# control.net
KiCad netlist of a schematic drawn in EAGLE
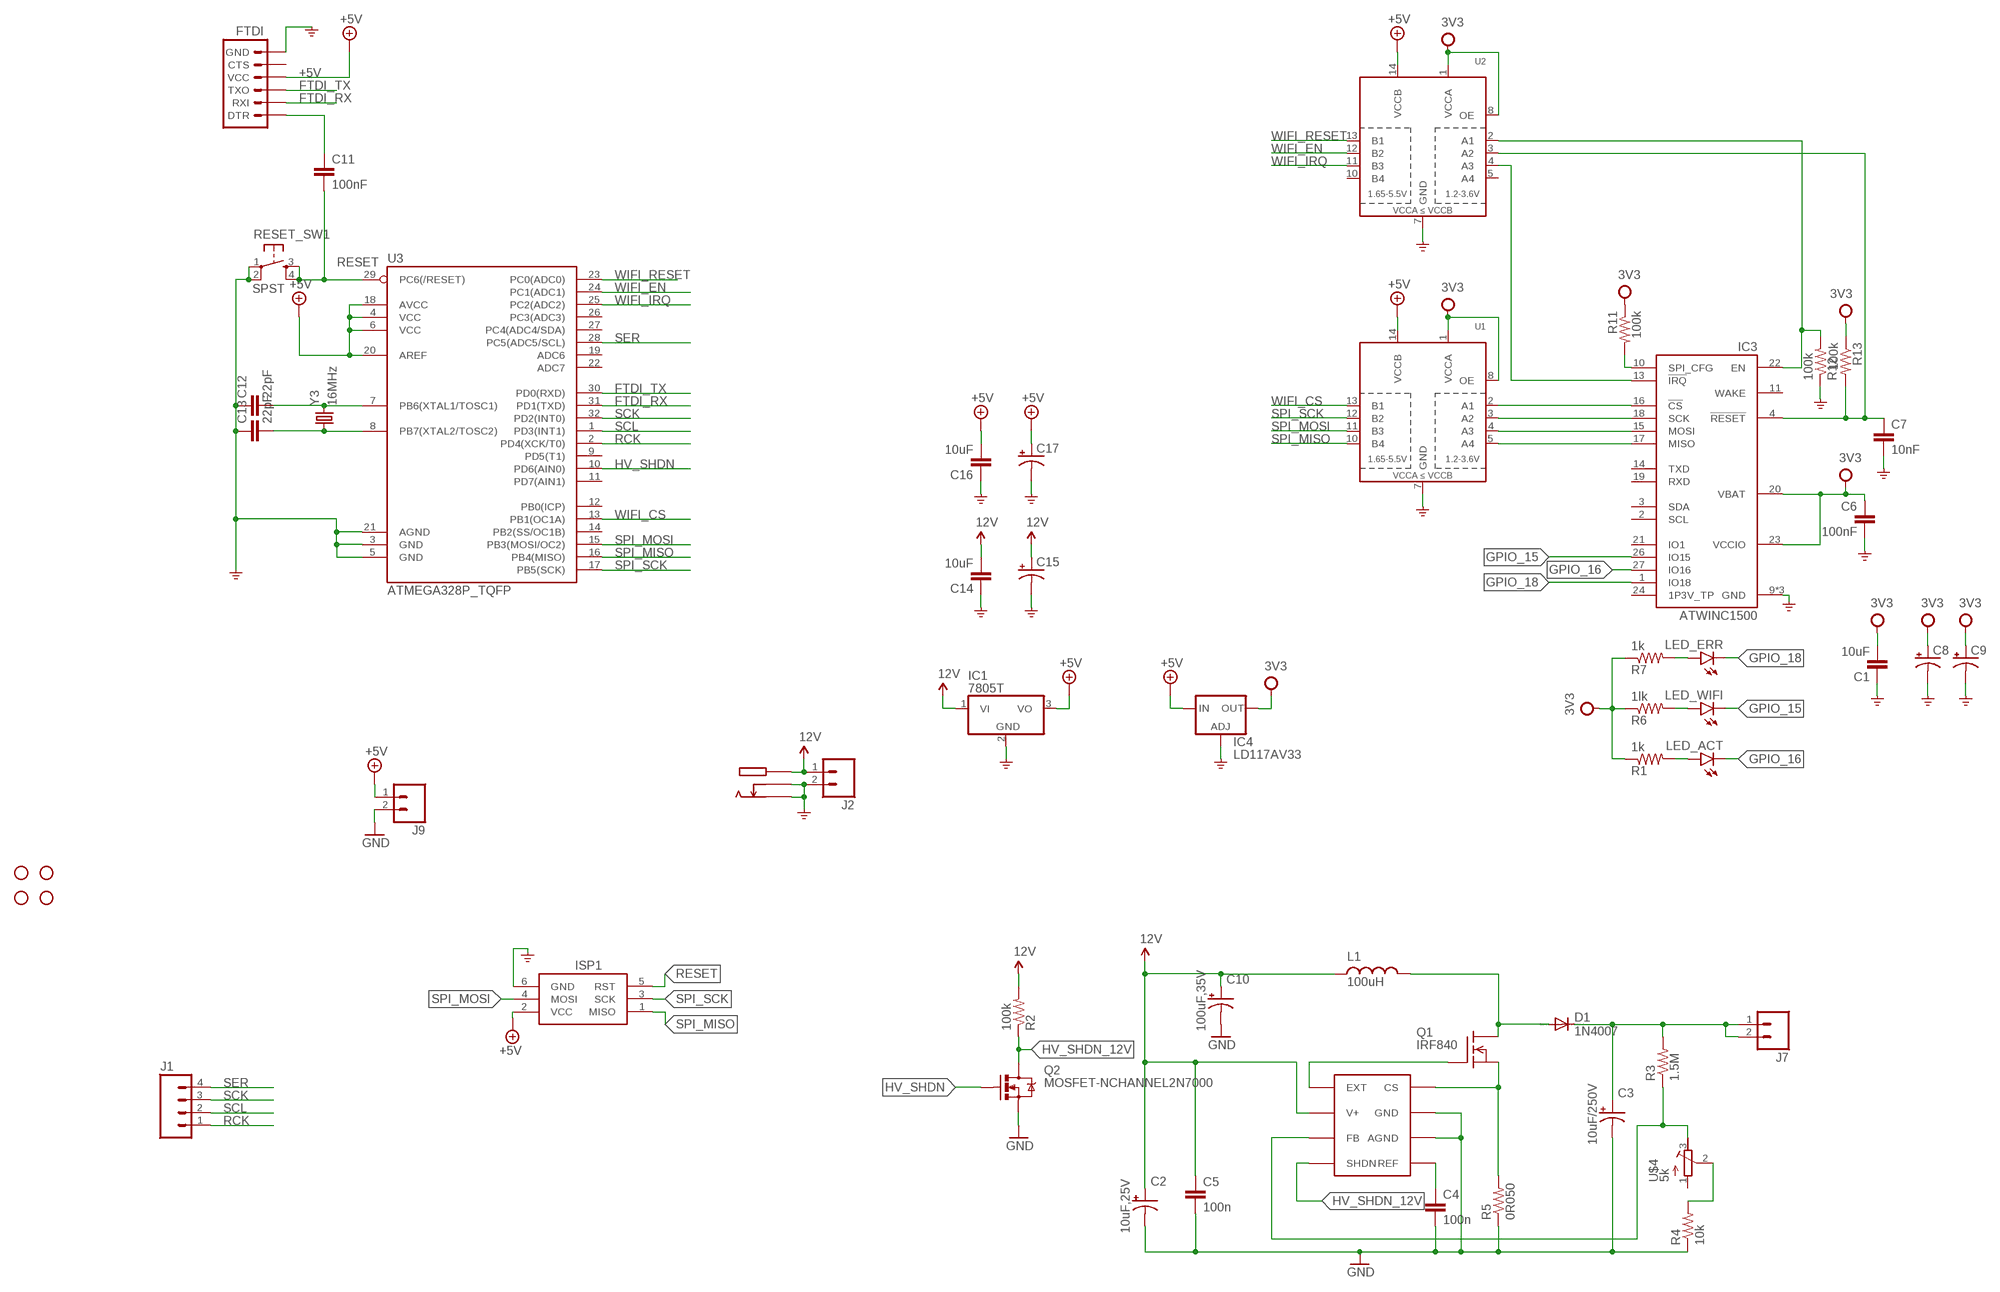
[diagram p0: schematic, sheet 1]

(export (version "E")
  (design (tool "Eeschema 10.0.6"))
  (components
    (comp (ref "C1")
      (value "10uF")
      (footprint "eagle-import:0805")
      (libsource (lib "eagle-import") (part "CAP0805"))
    )
    (comp (ref "C2")
      (value "10uF,25V")
      (footprint "eagle-import:CPOL-RADIAL-10UF-25V")
      (libsource (lib "eagle-import") (part "CAP_POLPTH2"))
    )
    (comp (ref "C3")
      (value "10uF/250V")
      (footprint "eagle-import:CPOL-RADIAL-10UF-25V")
      (libsource (lib "eagle-import") (part "CAP_POLPTH2"))
    )
    (comp (ref "C4")
      (value "100n")
      (footprint "eagle-import:CAP-PTH-SMALL")
      (libsource (lib "eagle-import") (part "SparkFun-Passives_CAPPTH"))
    )
    (comp (ref "C5")
      (value "100n")
      (footprint "eagle-import:CAP-PTH-SMALL")
      (libsource (lib "eagle-import") (part "SparkFun-Passives_CAPPTH"))
    )
    (comp (ref "C6")
      (value "100nF")
      (footprint "eagle-import:0805")
      (libsource (lib "eagle-import") (part "CAP0805"))
    )
    (comp (ref "C7")
      (value "10nF")
      (footprint "eagle-import:0805")
      (libsource (lib "eagle-import") (part "CAP0805"))
    )
    (comp (ref "C8")
      (value "CPOL-USE2,5-6E")
      (footprint "eagle-import:E2,5-6E")
      (libsource (lib "eagle-import") (part "CPOL-USE2,5-6E"))
    )
    (comp (ref "C9")
      (value "CPOL-USE2,5-6E")
      (footprint "eagle-import:E2,5-6E")
      (libsource (lib "eagle-import") (part "CPOL-USE2,5-6E"))
    )
    (comp (ref "C10")
      (value "100uF,35V")
      (footprint "eagle-import:CPOL-RADIAL-10UF-25V")
      (libsource (lib "eagle-import") (part "CAP_POLPTH2"))
    )
    (comp (ref "C11")
      (value "100nF")
      (footprint "eagle-import:0805")
      (libsource (lib "eagle-import") (part "CAP0805"))
    )
    (comp (ref "C12")
      (value "22pF")
      (footprint "eagle-import:0805")
      (libsource (lib "eagle-import") (part "CAP0805"))
    )
    (comp (ref "C13")
      (value "22pF")
      (footprint "eagle-import:0805")
      (libsource (lib "eagle-import") (part "CAP0805"))
    )
    (comp (ref "C14")
      (value "10uF")
      (footprint "eagle-import:0805")
      (libsource (lib "eagle-import") (part "CAP0805"))
    )
    (comp (ref "C15")
      (value "CPOL-USE2,5-6E")
      (footprint "eagle-import:E2,5-6E")
      (libsource (lib "eagle-import") (part "CPOL-USE2,5-6E"))
    )
    (comp (ref "C16")
      (value "10uF")
      (footprint "eagle-import:0805")
      (libsource (lib "eagle-import") (part "CAP0805"))
    )
    (comp (ref "C17")
      (value "CPOL-USE2,5-6E")
      (footprint "eagle-import:E2,5-6E")
      (libsource (lib "eagle-import") (part "CPOL-USE2,5-6E"))
    )
    (comp (ref "D1")
      (value "1N4007")
      (footprint "eagle-import:DO41-10")
      (libsource (lib "eagle-import") (part "1N4004"))
    )
    (comp (ref "FTDI")
      (value "ARDUINO_SERIAL_PROGRAMPTH")
      (footprint "eagle-import:1X06")
      (libsource (lib "eagle-import") (part "ARDUINO_SERIAL_PROGRAMPTH"))
    )
    (comp (ref "H1")
      (value "STAND-OFF")
      (footprint "eagle-import:STAND-OFF")
      (libsource (lib "eagle-import") (part "STAND-OFF"))
    )
    (comp (ref "H2")
      (value "STAND-OFF")
      (footprint "eagle-import:STAND-OFF")
      (libsource (lib "eagle-import") (part "STAND-OFF"))
    )
    (comp (ref "H3")
      (value "STAND-OFF")
      (footprint "eagle-import:STAND-OFF")
      (libsource (lib "eagle-import") (part "STAND-OFF"))
    )
    (comp (ref "H4")
      (value "STAND-OFF")
      (footprint "eagle-import:STAND-OFF")
      (libsource (lib "eagle-import") (part "STAND-OFF"))
    )
    (comp (ref "IC1")
      (value "7805T")
      (footprint "eagle-import:TO220H")
      (libsource (lib "eagle-import") (part "78T05"))
    )
    (comp (ref "IC3")
      (value "ATWINC1500")
      (footprint "eagle-import:ATWINC1500-MR210")
      (libsource (lib "eagle-import") (part "ATWINC1500"))
    )
    (comp (ref "IC4")
      (value "LD117AV33")
      (footprint "eagle-import:TO220L1")
      (libsource (lib "eagle-import") (part "LD117A?V33"))
    )
    (comp (ref "ISP1")
      (value "AVRISP-6")
      (footprint "eagle-import:AVRISP")
      (libsource (lib "eagle-import") (part "AVRISP-6"))
    )
    (comp (ref "J1")
      (value "M04PTH")
      (footprint "eagle-import:1X04")
      (libsource (lib "eagle-import") (part "M04PTH"))
    )
    (comp (ref "J2")
      (value "M02PTH")
      (footprint "eagle-import:1X02")
      (libsource (lib "eagle-import") (part "M02PTH"))
    )
    (comp (ref "J7")
      (value "M02PTH")
      (footprint "eagle-import:1X02")
      (libsource (lib "eagle-import") (part "M02PTH"))
    )
    (comp (ref "J9")
      (value "M02PTH")
      (footprint "eagle-import:1X02")
      (libsource (lib "eagle-import") (part "M02PTH"))
    )
    (comp (ref "L1")
      (value "100uH")
      (footprint "eagle-import:L-B82479")
      (libsource (lib "eagle-import") (part "L-SMT-POWER-B82479"))
    )
    (comp (ref "LED_ACT")
      (value "LED0603")
      (footprint "eagle-import:LED-0603")
      (libsource (lib "eagle-import") (part "LED0603"))
    )
    (comp (ref "LED_ERR")
      (value "LED0603")
      (footprint "eagle-import:LED-0603")
      (libsource (lib "eagle-import") (part "LED0603"))
    )
    (comp (ref "LED_WIFI")
      (value "LED0603")
      (footprint "eagle-import:LED-0603")
      (libsource (lib "eagle-import") (part "LED0603"))
    )
    (comp (ref "Q1")
      (value "IRF840")
      (footprint "eagle-import:TO220")
      (libsource (lib "eagle-import") (part "IRF840"))
    )
    (comp (ref "Q2")
      (value "MOSFET-NCHANNEL2N7000")
      (footprint "eagle-import:TO-92")
      (libsource (lib "eagle-import") (part "MOSFET-NCHANNEL2N7000"))
    )
    (comp (ref "R1")
      (value "1k")
      (footprint "eagle-import:0805")
      (libsource (lib "eagle-import") (part "RESISTOR0805-RES"))
    )
    (comp (ref "R2")
      (value "100k")
      (footprint "eagle-import:0805")
      (libsource (lib "eagle-import") (part "RESISTOR0805-RES"))
    )
    (comp (ref "R3")
      (value "1.5M")
      (footprint "eagle-import:AXIAL-0.4")
      (libsource (lib "eagle-import") (part "RESISTORPTH-1/4W"))
    )
    (comp (ref "R4")
      (value "10k")
      (footprint "eagle-import:AXIAL-0.4")
      (libsource (lib "eagle-import") (part "RESISTORPTH-1/4W"))
    )
    (comp (ref "R5")
      (value "0R050")
      (footprint "eagle-import:AXIAL-0.4")
      (libsource (lib "eagle-import") (part "RESISTORPTH-1/4W"))
    )
    (comp (ref "R6")
      (value "1lk")
      (footprint "eagle-import:0805")
      (libsource (lib "eagle-import") (part "RESISTOR0805-RES"))
    )
    (comp (ref "R7")
      (value "1k")
      (footprint "eagle-import:0805")
      (libsource (lib "eagle-import") (part "RESISTOR0805-RES"))
    )
    (comp (ref "R11")
      (value "100k")
      (footprint "eagle-import:0805")
      (libsource (lib "eagle-import") (part "RESISTOR0805-RES"))
    )
    (comp (ref "R12")
      (value "100k")
      (footprint "eagle-import:0805")
      (libsource (lib "eagle-import") (part "RESISTOR0805-RES"))
    )
    (comp (ref "R13")
      (value "100k")
      (footprint "eagle-import:0805")
      (libsource (lib "eagle-import") (part "RESISTOR0805-RES"))
    )
    (comp (ref "RESET_SW1")
      (value "SPST")
      (footprint "eagle-import:TAC-SWITCH-PTH")
      (libsource (lib "eagle-import") (part "TACTILE-SWITCH-PTH"))
    )
    (comp (ref "U$3")
      (value "MAX1771")
      (footprint "eagle-import:8-DIP")
      (libsource (lib "eagle-import") (part "MAX1771"))
    )
    (comp (ref "U$4")
      (value "5k")
      (footprint "eagle-import:RTRIM3362P")
      (libsource (lib "eagle-import") (part "RTRIM-3362P"))
    )
    (comp (ref "U$19")
      (value "PJ-044A")
      (footprint "eagle-import:PJ-044A")
      (libsource (lib "eagle-import") (part "PJ-044A"))
    )
    (comp (ref "U1")
      (value "TXB0104PWRSOIC14")
      (footprint "eagle-import:SO14")
      (libsource (lib "eagle-import") (part "TXB0104PWRSOIC14"))
    )
    (comp (ref "U2")
      (value "TXB0104PWRSOIC14")
      (footprint "eagle-import:SO14")
      (libsource (lib "eagle-import") (part "TXB0104PWRSOIC14"))
    )
    (comp (ref "U3")
      (value "ATMEGA328P_TQFP")
      (footprint "eagle-import:TQFP32-08")
      (libsource (lib "eagle-import") (part "ATMEGA328P_TQFP"))
    )
    (comp (ref "Y3")
      (value "16MHz")
      (footprint "eagle-import:HC49US")
      (libsource (lib "eagle-import") (part "CRYSTALHC49US"))
    )
  )
  (nets
    (net (code "1") (name "+5V") (class "Default")
      (node (ref "C16") (pin "2") (pinfunction "2_2") (pintype "passive"))
      (node (ref "C17") (pin "+") (pinfunction "+_+") (pintype "passive"))
      (node (ref "FTDI") (pin "4") (pinfunction "VCC_4") (pintype "passive"))
      (node (ref "IC1") (pin "3") (pinfunction "VO_3") (pintype "passive"))
      (node (ref "IC4") (pin "3") (pinfunction "IN_3") (pintype "input"))
      (node (ref "ISP1") (pin "2") (pinfunction "VCC_2") (pintype "power_in"))
      (node (ref "J9") (pin "1") (pinfunction "1_1") (pintype "passive"))
      (node (ref "U1") (pin "14") (pinfunction "VCCB_14") (pintype "bidirectional"))
      (node (ref "U2") (pin "14") (pinfunction "VCCB_14") (pintype "bidirectional"))
      (node (ref "U3") (pin "18") (pinfunction "AVCC_18") (pintype "bidirectional"))
      (node (ref "U3") (pin "20") (pinfunction "AREF_20") (pintype "bidirectional"))
      (node (ref "U3") (pin "4") (pinfunction "VCC_4") (pintype "bidirectional"))
      (node (ref "U3") (pin "6") (pinfunction "VCC_6") (pintype "bidirectional"))
    )
    (net (code "2") (name "/FTDI_RX") (class "Default")
      (node (ref "FTDI") (pin "2") (pinfunction "RXI_2") (pintype "passive"))
      (node (ref "U3") (pin "31") (pinfunction "PD1(TXD)_31") (pintype "bidirectional"))
    )
    (net (code "3") (name "/FTDI_TX") (class "Default")
      (node (ref "FTDI") (pin "3") (pinfunction "TXO_3") (pintype "passive"))
      (node (ref "U3") (pin "30") (pinfunction "PD0(RXD)_30") (pintype "bidirectional"))
    )
    (net (code "4") (name "/RCK") (class "Default")
      (node (ref "J1") (pin "1") (pinfunction "1_1") (pintype "passive"))
      (node (ref "U3") (pin "2") (pinfunction "PD4(XCK/T0)_2") (pintype "bidirectional"))
    )
    (net (code "5") (name "/SCK") (class "Default")
      (node (ref "J1") (pin "3") (pinfunction "3_3") (pintype "passive"))
      (node (ref "U3") (pin "32") (pinfunction "PD2(INT0)_32") (pintype "bidirectional"))
    )
    (net (code "6") (name "/SCL") (class "Default")
      (node (ref "J1") (pin "2") (pinfunction "2_2") (pintype "passive"))
      (node (ref "U3") (pin "1") (pinfunction "PD3(INT1)_1") (pintype "bidirectional"))
    )
    (net (code "7") (name "/SER") (class "Default")
      (node (ref "J1") (pin "4") (pinfunction "4_4") (pintype "passive"))
      (node (ref "U3") (pin "28") (pinfunction "PC5(ADC5/SCL)_28") (pintype "bidirectional"))
    )
    (net (code "8") (name "/WIFI_CS") (class "Default")
      (node (ref "U1") (pin "13") (pinfunction "B1_13") (pintype "bidirectional"))
      (node (ref "U3") (pin "13") (pinfunction "PB1(OC1A)_13") (pintype "bidirectional"))
    )
    (net (code "9") (name "/WIFI_EN") (class "Default")
      (node (ref "U2") (pin "12") (pinfunction "B2_12") (pintype "bidirectional"))
      (node (ref "U3") (pin "24") (pinfunction "PC1(ADC1)_24") (pintype "bidirectional"))
    )
    (net (code "10") (name "/WIFI_IRQ") (class "Default")
      (node (ref "U2") (pin "11") (pinfunction "B3_11") (pintype "bidirectional"))
      (node (ref "U3") (pin "25") (pinfunction "PC2(ADC2)_25") (pintype "bidirectional"))
    )
    (net (code "11") (name "/WIFI_RESET") (class "Default")
      (node (ref "U2") (pin "13") (pinfunction "B1_13") (pintype "bidirectional"))
      (node (ref "U3") (pin "23") (pinfunction "PC0(ADC0)_23") (pintype "bidirectional"))
    )
    (net (code "12") (name "3V3") (class "Default")
      (node (ref "C1") (pin "2") (pinfunction "2_2") (pintype "passive"))
      (node (ref "C6") (pin "1") (pinfunction "1_1") (pintype "passive"))
      (node (ref "C8") (pin "+") (pinfunction "+_+") (pintype "passive"))
      (node (ref "C9") (pin "+") (pinfunction "+_+") (pintype "passive"))
      (node (ref "IC3") (pin "20") (pinfunction "VBAT_20") (pintype "power_in"))
      (node (ref "IC3") (pin "23") (pinfunction "VCCIO_23") (pintype "power_in"))
      (node (ref "IC4") (pin "2") (pinfunction "OUT_2") (pintype "passive"))
      (node (ref "R1") (pin "1") (pinfunction "1_1") (pintype "passive"))
      (node (ref "R11") (pin "1") (pinfunction "1_1") (pintype "passive"))
      (node (ref "R13") (pin "1") (pinfunction "1_1") (pintype "passive"))
      (node (ref "R6") (pin "1") (pinfunction "1_1") (pintype "passive"))
      (node (ref "R7") (pin "1") (pinfunction "1_1") (pintype "passive"))
      (node (ref "U1") (pin "1") (pinfunction "VCCA_1") (pintype "bidirectional"))
      (node (ref "U1") (pin "8") (pinfunction "OE_8") (pintype "bidirectional"))
      (node (ref "U2") (pin "1") (pinfunction "VCCA_1") (pintype "bidirectional"))
      (node (ref "U2") (pin "8") (pinfunction "OE_8") (pintype "bidirectional"))
    )
    (net (code "13") (name "12V") (class "Default")
      (node (ref "C10") (pin "1") (pinfunction "+_1") (pintype "passive"))
      (node (ref "C14") (pin "2") (pinfunction "2_2") (pintype "passive"))
      (node (ref "C15") (pin "+") (pinfunction "+_+") (pintype "passive"))
      (node (ref "C2") (pin "1") (pinfunction "+_1") (pintype "passive"))
      (node (ref "C5") (pin "1") (pinfunction "1_1") (pintype "passive"))
      (node (ref "IC1") (pin "1") (pinfunction "VI_1") (pintype "input"))
      (node (ref "J2") (pin "1") (pinfunction "1_1") (pintype "passive"))
      (node (ref "L1") (pin "P$1") (pinfunction "1_P$1") (pintype "passive"))
      (node (ref "R2") (pin "2") (pinfunction "2_2") (pintype "passive"))
      (node (ref "U$19") (pin "1") (pinfunction "1_1") (pintype "bidirectional"))
      (node (ref "U$19") (pin "P1") (pinfunction "1_P1") (pintype "bidirectional"))
      (node (ref "U$3") (pin "V+") (pinfunction "V+_V+") (pintype "bidirectional"))
    )
    (net (code "14") (name "GND") (class "Default")
      (node (ref "C1") (pin "1") (pinfunction "1_1") (pintype "passive"))
      (node (ref "C10") (pin "2") (pinfunction "-_2") (pintype "passive"))
      (node (ref "C12") (pin "1") (pinfunction "1_1") (pintype "passive"))
      (node (ref "C13") (pin "1") (pinfunction "1_1") (pintype "passive"))
      (node (ref "C14") (pin "1") (pinfunction "1_1") (pintype "passive"))
      (node (ref "C15") (pin "-") (pinfunction "-_-") (pintype "passive"))
      (node (ref "C16") (pin "1") (pinfunction "1_1") (pintype "passive"))
      (node (ref "C17") (pin "-") (pinfunction "-_-") (pintype "passive"))
      (node (ref "C2") (pin "2") (pinfunction "-_2") (pintype "passive"))
      (node (ref "C3") (pin "2") (pinfunction "-_2") (pintype "passive"))
      (node (ref "C4") (pin "2") (pinfunction "2_2") (pintype "passive"))
      (node (ref "C5") (pin "2") (pinfunction "2_2") (pintype "passive"))
      (node (ref "C6") (pin "2") (pinfunction "2_2") (pintype "passive"))
      (node (ref "C7") (pin "2") (pinfunction "2_2") (pintype "passive"))
      (node (ref "C8") (pin "-") (pinfunction "-_-") (pintype "passive"))
      (node (ref "C9") (pin "-") (pinfunction "-_-") (pintype "passive"))
      (node (ref "FTDI") (pin "6") (pinfunction "GND_6") (pintype "passive"))
      (node (ref "IC1") (pin "2") (pinfunction "GND_2") (pintype "passive"))
      (node (ref "IC3") (pin "12") (pinfunction "GND_12") (pintype "power_in"))
      (node (ref "IC3") (pin "28") (pinfunction "GND_28") (pintype "power_in"))
      (node (ref "IC3") (pin "9") (pinfunction "GND_9") (pintype "power_in"))
      (node (ref "IC4") (pin "1") (pinfunction "ADJ_1") (pintype "input"))
      (node (ref "ISP1") (pin "6") (pinfunction "GND_6") (pintype "power_in"))
      (node (ref "J2") (pin "2") (pinfunction "2_2") (pintype "passive"))
      (node (ref "J9") (pin "2") (pinfunction "2_2") (pintype "passive"))
      (node (ref "Q2") (pin "1") (pinfunction "S_1") (pintype "passive"))
      (node (ref "R12") (pin "1") (pinfunction "1_1") (pintype "passive"))
      (node (ref "R4") (pin "P$1") (pinfunction "1_P$1") (pintype "passive"))
      (node (ref "R5") (pin "P$1") (pinfunction "1_P$1") (pintype "passive"))
      (node (ref "RESET_SW1") (pin "1") (pinfunction "1_1") (pintype "passive"))
      (node (ref "RESET_SW1") (pin "2") (pinfunction "2_2") (pintype "passive"))
      (node (ref "U$19") (pin "2") (pinfunction "2_2") (pintype "bidirectional"))
      (node (ref "U$19") (pin "3") (pinfunction "3_3") (pintype "bidirectional"))
      (node (ref "U$19") (pin "P2") (pinfunction "2_P2") (pintype "bidirectional"))
      (node (ref "U$19") (pin "P3") (pinfunction "3_P3") (pintype "bidirectional"))
      (node (ref "U$3") (pin "AGND") (pinfunction "AGND_AGND") (pintype "bidirectional"))
      (node (ref "U$3") (pin "GND") (pinfunction "GND_GND") (pintype "bidirectional"))
      (node (ref "U1") (pin "7") (pinfunction "GND_7") (pintype "bidirectional"))
      (node (ref "U2") (pin "7") (pinfunction "GND_7") (pintype "bidirectional"))
      (node (ref "U3") (pin "21") (pinfunction "AGND_21") (pintype "bidirectional"))
      (node (ref "U3") (pin "3") (pinfunction "GND_3") (pintype "bidirectional"))
      (node (ref "U3") (pin "5") (pinfunction "GND_5") (pintype "bidirectional"))
    )
    (net (code "15") (name "GPIO_15") (class "Default")
      (node (ref "IC3") (pin "26") (pinfunction "IO15_26") (pintype "bidirectional"))
      (node (ref "LED_WIFI") (pin "C") (pinfunction "C_C") (pintype "passive"))
    )
    (net (code "16") (name "GPIO_16") (class "Default")
      (node (ref "IC3") (pin "27") (pinfunction "IO16_27") (pintype "bidirectional"))
      (node (ref "LED_ACT") (pin "C") (pinfunction "C_C") (pintype "passive"))
    )
    (net (code "17") (name "GPIO_18") (class "Default")
      (node (ref "IC3") (pin "1") (pinfunction "IO18_1") (pintype "bidirectional"))
      (node (ref "LED_ERR") (pin "C") (pinfunction "C_C") (pintype "passive"))
    )
    (net (code "18") (name "HV_SHDN") (class "Default")
      (node (ref "Q2") (pin "2") (pinfunction "G_2") (pintype "passive"))
      (node (ref "U3") (pin "10") (pinfunction "PD6(AIN0)_10") (pintype "bidirectional"))
    )
    (net (code "19") (name "HV_SHDN_12V") (class "Default")
      (node (ref "Q2") (pin "3") (pinfunction "D_3") (pintype "passive"))
      (node (ref "R2") (pin "1") (pinfunction "1_1") (pintype "passive"))
      (node (ref "U$3") (pin "SHDN") (pinfunction "SHDN_SHDN") (pintype "bidirectional"))
    )
    (net (code "20") (name "Net-(C3-+)") (class "Default")
      (node (ref "C3") (pin "1") (pinfunction "+_1") (pintype "passive"))
      (node (ref "D1") (pin "C") (pinfunction "C_C") (pintype "passive"))
      (node (ref "J7") (pin "1") (pinfunction "1_1") (pintype "passive"))
      (node (ref "J7") (pin "2") (pinfunction "2_2") (pintype "passive"))
      (node (ref "R3") (pin "P$2") (pinfunction "2_P$2") (pintype "passive"))
    )
    (net (code "21") (name "Net-(C4-Pad1)") (class "Default")
      (node (ref "C4") (pin "1") (pinfunction "1_1") (pintype "passive"))
      (node (ref "U$3") (pin "REF") (pinfunction "REF_REF") (pintype "bidirectional"))
    )
    (net (code "22") (name "Net-(FTDI-DTR)") (class "Default")
      (node (ref "C11") (pin "1") (pinfunction "1_1") (pintype "passive"))
      (node (ref "FTDI") (pin "1") (pinfunction "DTR_1") (pintype "passive"))
    )
    (net (code "23") (name "Net-(IC3-EN)") (class "Default")
      (node (ref "IC3") (pin "22") (pinfunction "EN_22") (pintype "input"))
      (node (ref "R12") (pin "2") (pinfunction "2_2") (pintype "passive"))
      (node (ref "U2") (pin "2") (pinfunction "A1_2") (pintype "bidirectional"))
    )
    (net (code "24") (name "Net-(IC3-MISO)") (class "Default")
      (node (ref "IC3") (pin "17") (pinfunction "MISO_17") (pintype "output"))
      (node (ref "U1") (pin "5") (pinfunction "A4_5") (pintype "bidirectional"))
    )
    (net (code "25") (name "Net-(IC3-MOSI)") (class "Default")
      (node (ref "IC3") (pin "15") (pinfunction "MOSI_15") (pintype "input"))
      (node (ref "U1") (pin "4") (pinfunction "A3_4") (pintype "bidirectional"))
    )
    (net (code "26") (name "Net-(IC3-SCK)") (class "Default")
      (node (ref "IC3") (pin "18") (pinfunction "SCK_18") (pintype "input"))
      (node (ref "U1") (pin "3") (pinfunction "A2_3") (pintype "bidirectional"))
    )
    (net (code "27") (name "Net-(IC3-SPI_CFG)") (class "Default")
      (node (ref "IC3") (pin "10") (pinfunction "SPI_CFG_10") (pintype "input"))
      (node (ref "R11") (pin "2") (pinfunction "2_2") (pintype "passive"))
    )
    (net (code "28") (name "Net-(IC3-~{CS})") (class "Default")
      (node (ref "IC3") (pin "16") (pinfunction "~{CS}_16") (pintype "input"))
      (node (ref "U1") (pin "2") (pinfunction "A1_2") (pintype "bidirectional"))
    )
    (net (code "29") (name "Net-(IC3-~{IRQ})") (class "Default")
      (node (ref "IC3") (pin "13") (pinfunction "~{IRQ}_13") (pintype "output"))
      (node (ref "U2") (pin "4") (pinfunction "A3_4") (pintype "bidirectional"))
    )
    (net (code "30") (name "Net-(IC3-~{RESET})") (class "Default")
      (node (ref "C7") (pin "1") (pinfunction "1_1") (pintype "passive"))
      (node (ref "IC3") (pin "4") (pinfunction "~{RESET}_4") (pintype "input"))
      (node (ref "R13") (pin "2") (pinfunction "2_2") (pintype "passive"))
      (node (ref "U2") (pin "3") (pinfunction "A2_3") (pintype "bidirectional"))
    )
    (net (code "31") (name "Net-(L1-2)") (class "Default")
      (node (ref "D1") (pin "A") (pinfunction "A_A") (pintype "passive"))
      (node (ref "L1") (pin "P$2") (pinfunction "2_P$2") (pintype "passive"))
      (node (ref "Q1") (pin "2") (pinfunction "D_2") (pintype "passive"))
    )
    (net (code "32") (name "Net-(LED_ACT-PadA)") (class "Default")
      (node (ref "LED_ACT") (pin "A") (pinfunction "A_A") (pintype "passive"))
      (node (ref "R1") (pin "2") (pinfunction "2_2") (pintype "passive"))
    )
    (net (code "33") (name "Net-(LED_ERR-PadA)") (class "Default")
      (node (ref "LED_ERR") (pin "A") (pinfunction "A_A") (pintype "passive"))
      (node (ref "R7") (pin "2") (pinfunction "2_2") (pintype "passive"))
    )
    (net (code "34") (name "Net-(LED_WIFI-PadA)") (class "Default")
      (node (ref "LED_WIFI") (pin "A") (pinfunction "A_A") (pintype "passive"))
      (node (ref "R6") (pin "2") (pinfunction "2_2") (pintype "passive"))
    )
    (net (code "35") (name "Net-(Q1-G)") (class "Default")
      (node (ref "Q1") (pin "1") (pinfunction "G_1") (pintype "passive"))
      (node (ref "U$3") (pin "EXT") (pinfunction "EXT_EXT") (pintype "bidirectional"))
    )
    (net (code "36") (name "Net-(Q1-S)") (class "Default")
      (node (ref "Q1") (pin "3") (pinfunction "S_3") (pintype "passive"))
      (node (ref "R5") (pin "P$2") (pinfunction "2_P$2") (pintype "passive"))
      (node (ref "U$3") (pin "CS") (pinfunction "CS_CS") (pintype "bidirectional"))
    )
    (net (code "37") (name "Net-(R3-1)") (class "Default")
      (node (ref "R3") (pin "P$1") (pinfunction "1_P$1") (pintype "passive"))
      (node (ref "U$3") (pin "FB") (pinfunction "FB_FB") (pintype "bidirectional"))
      (node (ref "U$4") (pin "3") (pinfunction "3_3") (pintype "passive"))
    )
    (net (code "38") (name "Net-(R4-2)") (class "Default")
      (node (ref "R4") (pin "P$2") (pinfunction "2_P$2") (pintype "passive"))
      (node (ref "U$4") (pin "2") (pinfunction "2_2") (pintype "passive"))
    )
    (net (code "39") (name "Net-(U3-PB6(XTAL1{slash}TOSC1))") (class "Default")
      (node (ref "C12") (pin "2") (pinfunction "2_2") (pintype "passive"))
      (node (ref "U3") (pin "7") (pinfunction "PB6(XTAL1/TOSC1)_7") (pintype "bidirectional"))
      (node (ref "Y3") (pin "2") (pinfunction "2_2") (pintype "passive"))
    )
    (net (code "40") (name "Net-(U3-PB7(XTAL2{slash}TOSC2))") (class "Default")
      (node (ref "C13") (pin "2") (pinfunction "2_2") (pintype "passive"))
      (node (ref "U3") (pin "8") (pinfunction "PB7(XTAL2/TOSC2)_8") (pintype "bidirectional"))
      (node (ref "Y3") (pin "1") (pinfunction "1_1") (pintype "passive"))
    )
    (net (code "41") (name "RESET") (class "Default")
      (node (ref "C11") (pin "2") (pinfunction "2_2") (pintype "passive"))
      (node (ref "ISP1") (pin "5") (pinfunction "RST_5") (pintype "output"))
      (node (ref "RESET_SW1") (pin "3") (pinfunction "3_3") (pintype "passive"))
      (node (ref "RESET_SW1") (pin "4") (pinfunction "4_4") (pintype "passive"))
      (node (ref "U3") (pin "29") (pinfunction "PC6(/RESET)_29") (pintype "bidirectional"))
    )
    (net (code "42") (name "SPI_MISO") (class "Default")
      (node (ref "ISP1") (pin "1") (pinfunction "MISO_1") (pintype "input"))
      (node (ref "U1") (pin "10") (pinfunction "B4_10") (pintype "bidirectional"))
      (node (ref "U3") (pin "16") (pinfunction "PB4(MISO)_16") (pintype "bidirectional"))
    )
    (net (code "43") (name "SPI_MOSI") (class "Default")
      (node (ref "ISP1") (pin "4") (pinfunction "MOSI_4") (pintype "output"))
      (node (ref "U1") (pin "11") (pinfunction "B3_11") (pintype "bidirectional"))
      (node (ref "U3") (pin "15") (pinfunction "PB3(MOSI/OC2)_15") (pintype "bidirectional"))
    )
    (net (code "44") (name "SPI_SCK") (class "Default")
      (node (ref "ISP1") (pin "3") (pinfunction "SCK_3") (pintype "output"))
      (node (ref "U1") (pin "12") (pinfunction "B2_12") (pintype "bidirectional"))
      (node (ref "U3") (pin "17") (pinfunction "PB5(SCK)_17") (pintype "bidirectional"))
    )
    (net (code "45") (name "unconnected-(FTDI-CTS-Pad5)") (class "Default")
      (node (ref "FTDI") (pin "5") (pinfunction "CTS_5") (pintype "passive"))
    )
    (net (code "46") (name "unconnected-(IC3-1P3V_TP-Pad24)") (class "Default")
      (node (ref "IC3") (pin "24") (pinfunction "1P3V_TP_24") (pintype "bidirectional"))
    )
    (net (code "47") (name "unconnected-(IC3-IO1-Pad21)") (class "Default")
      (node (ref "IC3") (pin "21") (pinfunction "IO1_21") (pintype "input"))
    )
    (net (code "48") (name "unconnected-(IC3-RXD-Pad19)") (class "Default")
      (node (ref "IC3") (pin "19") (pinfunction "RXD_19") (pintype "input"))
    )
    (net (code "49") (name "unconnected-(IC3-SCL-Pad2)") (class "Default")
      (node (ref "IC3") (pin "2") (pinfunction "SCL_2") (pintype "bidirectional"))
    )
    (net (code "50") (name "unconnected-(IC3-SDA-Pad3)") (class "Default")
      (node (ref "IC3") (pin "3") (pinfunction "SDA_3") (pintype "bidirectional"))
    )
    (net (code "51") (name "unconnected-(IC3-TXD-Pad14)") (class "Default")
      (node (ref "IC3") (pin "14") (pinfunction "TXD_14") (pintype "output"))
    )
    (net (code "52") (name "unconnected-(IC3-WAKE-Pad11)") (class "Default")
      (node (ref "IC3") (pin "11") (pinfunction "WAKE_11") (pintype "input"))
    )
    (net (code "53") (name "unconnected-(U$4-Pad1)") (class "Default")
      (node (ref "U$4") (pin "1") (pinfunction "1_1") (pintype "passive"))
    )
    (net (code "54") (name "unconnected-(U2-A4-Pad5)") (class "Default")
      (node (ref "U2") (pin "5") (pinfunction "A4_5") (pintype "bidirectional"))
    )
    (net (code "55") (name "unconnected-(U2-B4-Pad10)") (class "Default")
      (node (ref "U2") (pin "10") (pinfunction "B4_10") (pintype "bidirectional"))
    )
    (net (code "56") (name "unconnected-(U3-ADC6-Pad19)") (class "Default")
      (node (ref "U3") (pin "19") (pinfunction "ADC6_19") (pintype "bidirectional"))
    )
    (net (code "57") (name "unconnected-(U3-ADC7-Pad22)") (class "Default")
      (node (ref "U3") (pin "22") (pinfunction "ADC7_22") (pintype "bidirectional"))
    )
    (net (code "58") (name "unconnected-(U3-PB0(ICP)-Pad12)") (class "Default")
      (node (ref "U3") (pin "12") (pinfunction "PB0(ICP)_12") (pintype "bidirectional"))
    )
    (net (code "59") (name "unconnected-(U3-PB2(SS{slash}OC1B)-Pad14)") (class "Default")
      (node (ref "U3") (pin "14") (pinfunction "PB2(SS/OC1B)_14") (pintype "bidirectional"))
    )
    (net (code "60") (name "unconnected-(U3-PC3(ADC3)-Pad26)") (class "Default")
      (node (ref "U3") (pin "26") (pinfunction "PC3(ADC3)_26") (pintype "bidirectional"))
    )
    (net (code "61") (name "unconnected-(U3-PC4(ADC4{slash}SDA)-Pad27)") (class "Default")
      (node (ref "U3") (pin "27") (pinfunction "PC4(ADC4/SDA)_27") (pintype "bidirectional"))
    )
    (net (code "62") (name "unconnected-(U3-PD5(T1)-Pad9)") (class "Default")
      (node (ref "U3") (pin "9") (pinfunction "PD5(T1)_9") (pintype "bidirectional"))
    )
    (net (code "63") (name "unconnected-(U3-PD7(AIN1)-Pad11)") (class "Default")
      (node (ref "U3") (pin "11") (pinfunction "PD7(AIN1)_11") (pintype "bidirectional"))
    )
  )
)
